# ThermocoupleTestBoard_2023_10_08_A.net
KiCad netlist of a schematic drawn in EAGLE
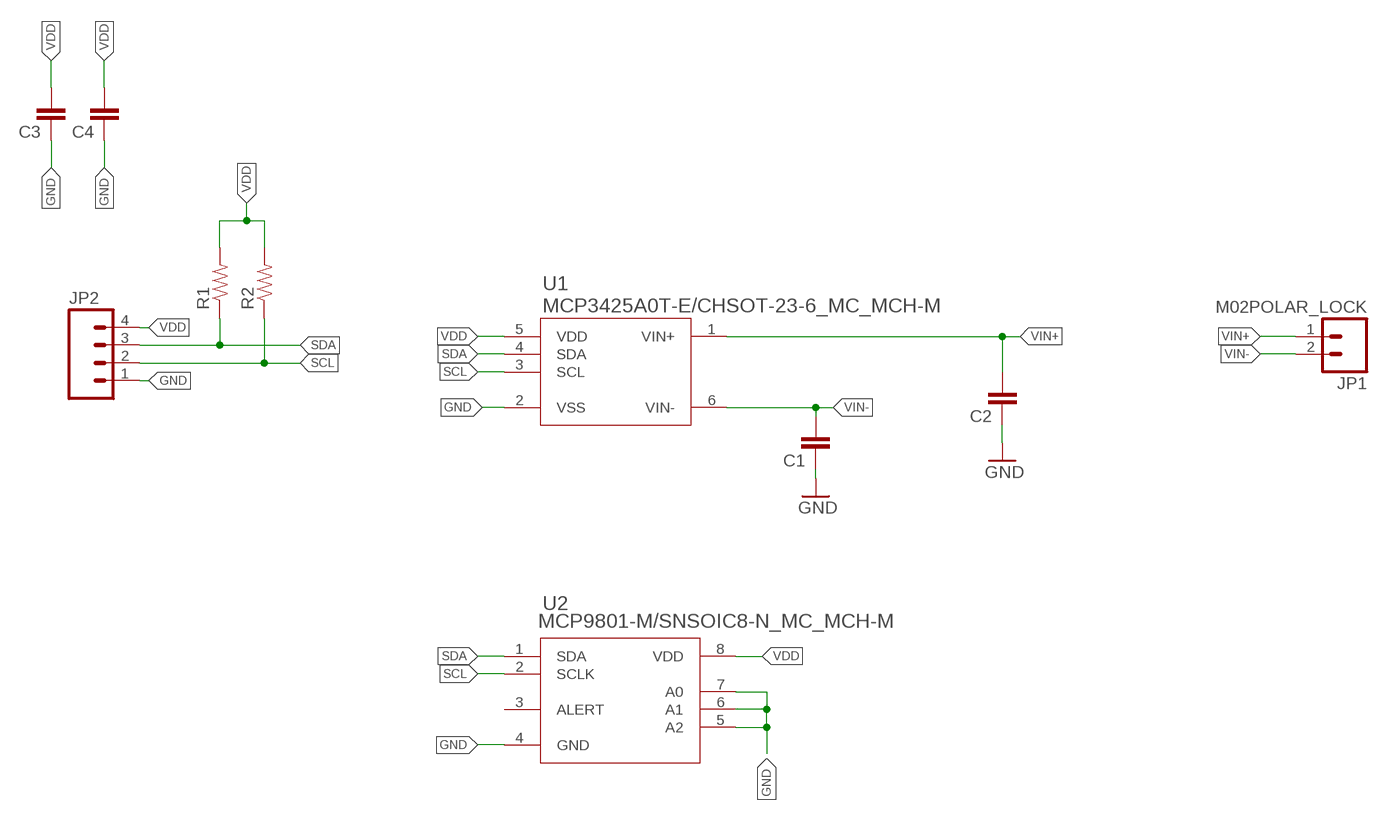
[diagram p0: schematic, sheet 1]

(export (version "E")
  (design (tool "Eeschema 10.0.6"))
  (components
    (comp (ref "C1")
      (value "CAP1206")
      (footprint "eagle-import:1206")
      (libsource (lib "eagle-import") (part "CAP1206"))
    )
    (comp (ref "C2")
      (value "CAP1206")
      (footprint "eagle-import:1206")
      (libsource (lib "eagle-import") (part "CAP1206"))
    )
    (comp (ref "C3")
      (value "CAP1206")
      (footprint "eagle-import:1206")
      (libsource (lib "eagle-import") (part "CAP1206"))
    )
    (comp (ref "C4")
      (value "CAP1206")
      (footprint "eagle-import:1206")
      (libsource (lib "eagle-import") (part "CAP1206"))
    )
    (comp (ref "JP1")
      (value "M02POLAR_LOCK")
      (footprint "eagle-import:MOLEX-1X2_LOCK")
      (libsource (lib "eagle-import") (part "M02POLAR_LOCK"))
    )
    (comp (ref "JP2")
      (value "M04LOCK")
      (footprint "eagle-import:1X04_LOCK")
      (libsource (lib "eagle-import") (part "M04LOCK"))
    )
    (comp (ref "R1")
      (value "RESISTOR1206")
      (footprint "eagle-import:1206")
      (libsource (lib "eagle-import") (part "RESISTOR1206"))
    )
    (comp (ref "R2")
      (value "RESISTOR1206")
      (footprint "eagle-import:1206")
      (libsource (lib "eagle-import") (part "RESISTOR1206"))
    )
    (comp (ref "U1")
      (value "MCP3425A0T-E/CHSOT-23-6_MC_MCH-M")
      (footprint "eagle-import:SOT-23-6_MC_MCH-M")
      (fields
        (field (name "MANUFACTURER_PART_NUMBER") "MCP3425A0T-E/CH")
        (field (name "COPYRIGHT") "Copyright (C) 2023 Ultra Librarian. All rights reserved.")
      )
      (libsource (lib "eagle-import") (part "MCP3425A0T-E/CHSOT-23-6_MC_MCH-M"))
    )
    (comp (ref "U2")
      (value "MCP9801-M/SNSOIC8-N_MC_MCH-M")
      (footprint "eagle-import:SOIC8-N_MC_MCH-M")
      (fields
        (field (name "MANUFACTURER_PART_NUMBER") "MCP9801-M/SN")
        (field (name "COPYRIGHT") "Copyright (C) 2023 Ultra Librarian. All rights reserved.")
      )
      (libsource (lib "eagle-import") (part "MCP9801-M/SNSOIC8-N_MC_MCH-M"))
    )
  )
  (nets
    (net (code "1") (name "GND") (class "Default")
      (node (ref "C1") (pin "1") (pinfunction "1_1") (pintype "passive"))
      (node (ref "C2") (pin "1") (pinfunction "1_1") (pintype "passive"))
      (node (ref "C3") (pin "1") (pinfunction "1_1") (pintype "passive"))
      (node (ref "C4") (pin "1") (pinfunction "1_1") (pintype "passive"))
      (node (ref "JP2") (pin "1") (pinfunction "1_1") (pintype "passive"))
      (node (ref "U1") (pin "2") (pinfunction "VSS_2") (pintype "passive"))
      (node (ref "U2") (pin "4") (pinfunction "GND_4") (pintype "passive"))
      (node (ref "U2") (pin "5") (pinfunction "A2_5") (pintype "passive"))
      (node (ref "U2") (pin "6") (pinfunction "A1_6") (pintype "passive"))
      (node (ref "U2") (pin "7") (pinfunction "A0_7") (pintype "passive"))
    )
    (net (code "2") (name "SCL") (class "Default")
      (node (ref "JP2") (pin "2") (pinfunction "2_2") (pintype "passive"))
      (node (ref "R2") (pin "1") (pinfunction "1_1") (pintype "passive"))
      (node (ref "U1") (pin "3") (pinfunction "SCL_3") (pintype "passive"))
      (node (ref "U2") (pin "2") (pinfunction "SCLK_2") (pintype "passive"))
    )
    (net (code "3") (name "SDA") (class "Default")
      (node (ref "JP2") (pin "3") (pinfunction "3_3") (pintype "passive"))
      (node (ref "R1") (pin "1") (pinfunction "1_1") (pintype "passive"))
      (node (ref "U1") (pin "4") (pinfunction "SDA_4") (pintype "passive"))
      (node (ref "U2") (pin "1") (pinfunction "SDA_1") (pintype "passive"))
    )
    (net (code "4") (name "VDD") (class "Default")
      (node (ref "C3") (pin "2") (pinfunction "2_2") (pintype "passive"))
      (node (ref "C4") (pin "2") (pinfunction "2_2") (pintype "passive"))
      (node (ref "JP2") (pin "4") (pinfunction "4_4") (pintype "passive"))
      (node (ref "R1") (pin "2") (pinfunction "2_2") (pintype "passive"))
      (node (ref "R2") (pin "2") (pinfunction "2_2") (pintype "passive"))
      (node (ref "U1") (pin "5") (pinfunction "VDD_5") (pintype "passive"))
      (node (ref "U2") (pin "8") (pinfunction "VDD_8") (pintype "passive"))
    )
    (net (code "5") (name "VIN+") (class "Default")
      (node (ref "C2") (pin "2") (pinfunction "2_2") (pintype "passive"))
      (node (ref "JP1") (pin "1") (pinfunction "1_1") (pintype "passive"))
      (node (ref "U1") (pin "1") (pinfunction "VIN+_1") (pintype "passive"))
    )
    (net (code "6") (name "VIN-") (class "Default")
      (node (ref "C1") (pin "2") (pinfunction "2_2") (pintype "passive"))
      (node (ref "JP1") (pin "2") (pinfunction "2_2") (pintype "passive"))
      (node (ref "U1") (pin "6") (pinfunction "VIN-_6") (pintype "passive"))
    )
    (net (code "7") (name "unconnected-(U2-ALERT-Pad3)") (class "Default")
      (node (ref "U2") (pin "3") (pinfunction "ALERT_3") (pintype "passive"))
    )
  )
)
